# Atomic_V1_0.net
KiCad netlist of a schematic drawn in EAGLE
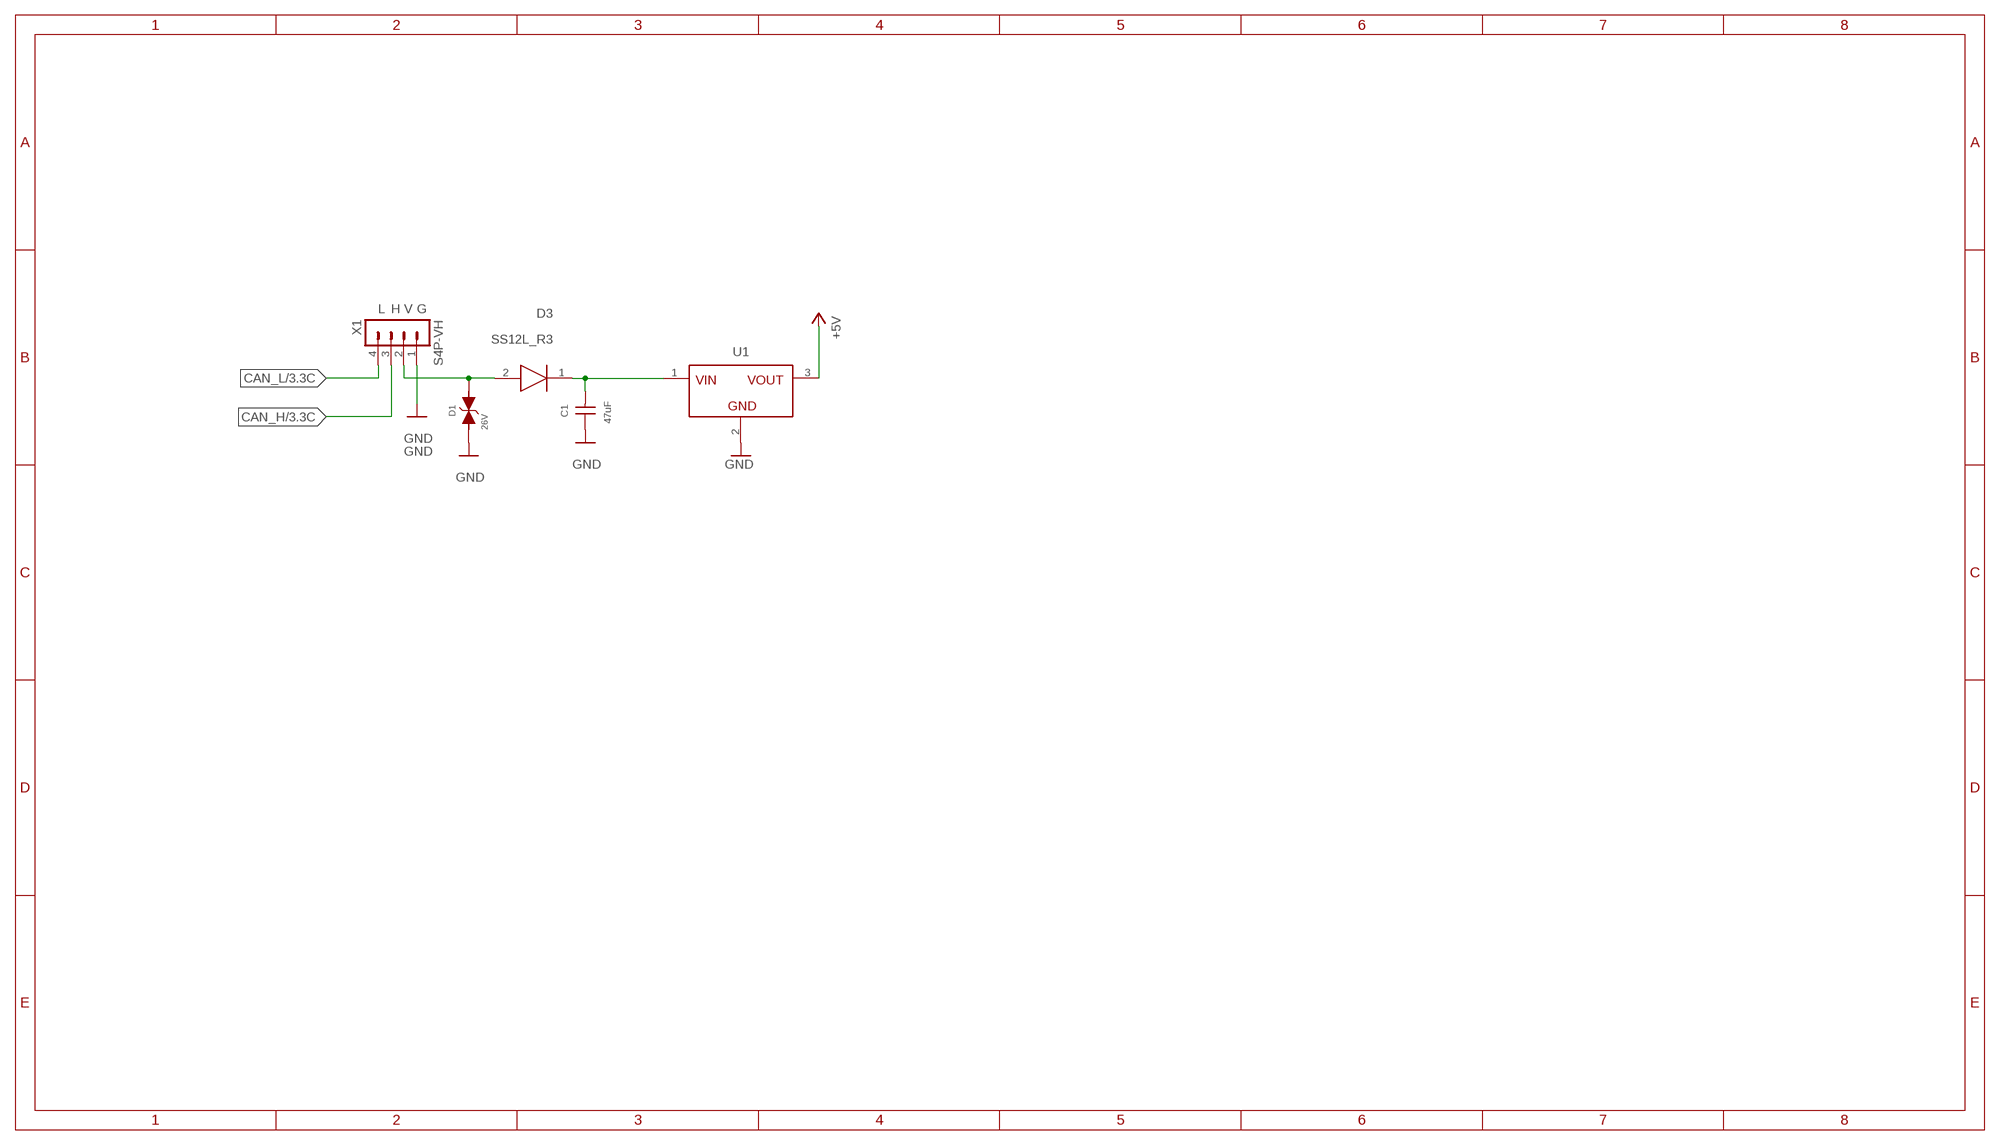
[diagram p0: schematic, sheet 1]
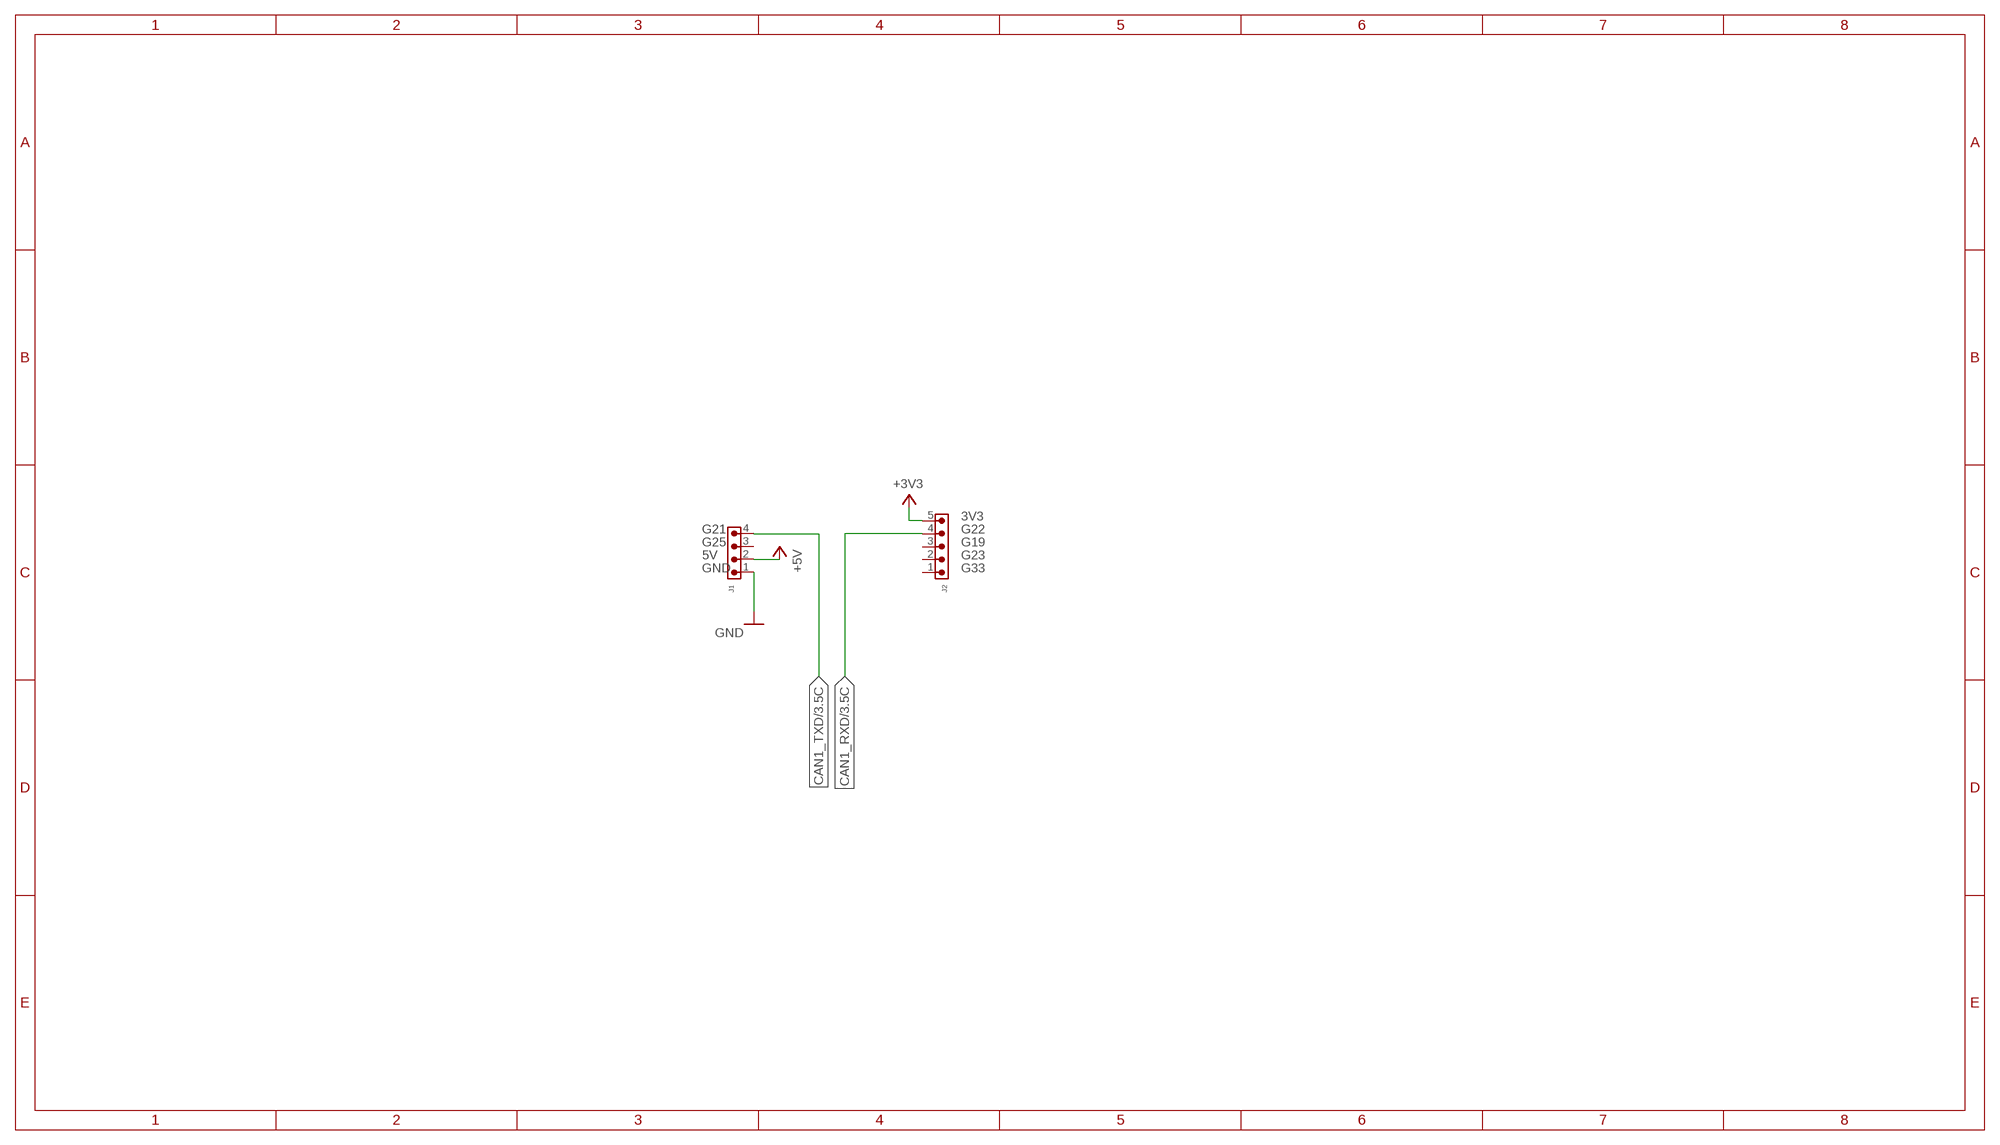
[diagram p1: schematic, sheet 2]
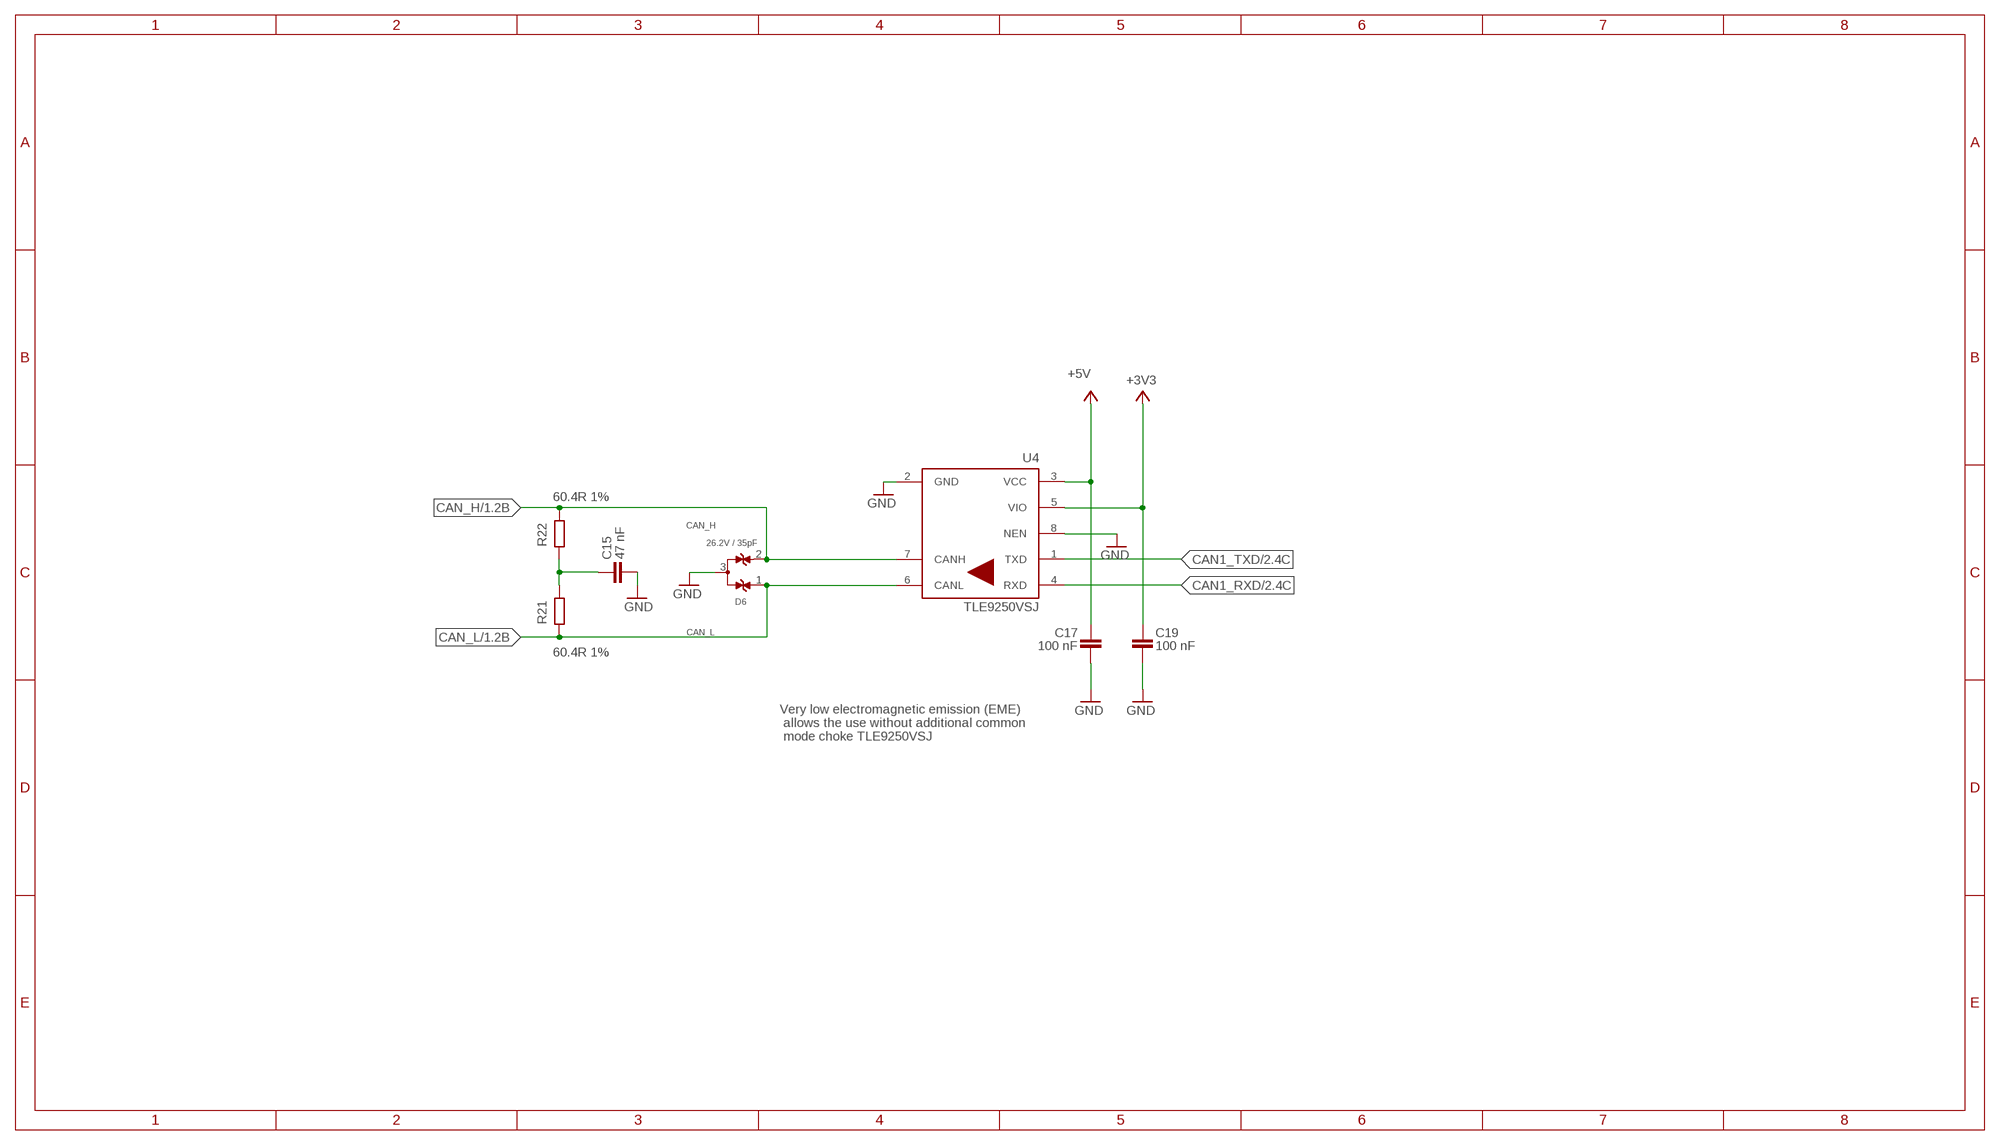
[diagram p2: schematic, sheet 3]

(export (version "E")
  (design (tool "Eeschema 10.0.6"))
  (components
    (comp (ref "C1")
      (value "47uF")
      (footprint "eagle-import:WCAP-CSGP_1210_H2.5")
      (libsource (lib "eagle-import") (part "WCAP-CSGP_1210_H2.5_25V(DC)_885012109014"))
    )
    (comp (ref "D1")
      (value "26V")
      (footprint "eagle-import:WE-TVSP_DO-214AC_BIDIRECTIONAL")
      (libsource (lib "eagle-import") (part "WE-TVSP_DO-214AC_400W_BI_824501261"))
    )
    (comp (ref "D3")
      (value "SS12L_R3")
      (footprint "eagle-import:SODFL3618X143N")
      (fields
        (field (name "MANUFACTURER_PART_NUMBER") "SS12L R3")
        (field (name "MOUSER_PART_NUMBER") "821-SS12LR3")
      )
      (libsource (lib "eagle-import") (part "SS12L_R3"))
    )
    (comp (ref "U1")
      (value "MAGI³C-FDSM_SIP-3_173010542_173XXXX42")
      (footprint "eagle-import:MAGI³C-FDSM_173XXXX42")
      (libsource (lib "eagle-import") (part "MAGI³C-FDSM_SIP-3_173XXXX42_173010542"))
    )
    (comp (ref "X1")
      (value "S4P-VH")
      (footprint "eagle-import:S4P-VH")
      (libsource (lib "eagle-import") (part "S4P-VH"))
    )
    (comp (ref "C15")
      (value "47 nF")
      (footprint "eagle-import:WCAP-CSGP_0402")
      (libsource (lib "eagle-import") (part "WCAP-CSGP_0402_25V(DC)_885012205054"))
    )
    (comp (ref "C17")
      (value "100 nF")
      (footprint "eagle-import:WCAP-CSGP_0402")
      (libsource (lib "eagle-import") (part "WCAP-CSGP_0402_16V(DC)_885012205037"))
    )
    (comp (ref "C19")
      (value "100 nF")
      (footprint "eagle-import:WCAP-CSGP_0402")
      (libsource (lib "eagle-import") (part "WCAP-CSGP_0402_16V(DC)_885012205037"))
    )
    (comp (ref "D6")
      (value "26.2V / 35pF")
      (footprint "eagle-import:WE-TVS_SOT23-3L")
      (libsource (lib "eagle-import") (part "WE-TVS_SOT23-3L_824098024"))
    )
    (comp (ref "R21")
      (value "60.4R 1%")
      (footprint "eagle-import:WCAP-CSRF_0402")
      (fields (field (name "N") "SMD 0402 60.4ohms 1% AEC-Q200"))
      (libsource (lib "eagle-import") (part "R-0402_60.4OHMS_1%_AEC-Q200"))
    )
    (comp (ref "R22")
      (value "60.4R 1%")
      (footprint "eagle-import:WCAP-CSRF_0402")
      (fields (field (name "N") "SMD 0402 60.4ohms 1% AEC-Q200"))
      (libsource (lib "eagle-import") (part "R-0402_60.4OHMS_1%_AEC-Q200"))
    )
    (comp (ref "U4")
      (value "TLE9250VSJ")
      (footprint "eagle-import:SOIC127P602X173-8N-V")
      (libsource (lib "eagle-import") (part "TLE9250VSJ"))
    )
    (comp (ref "J1")
      (value "6130XX11121_61300411121")
      (footprint "eagle-import:61300411121")
      (libsource (lib "eagle-import") (part "6130XX11121_61300411121"))
    )
    (comp (ref "J2")
      (value "6130XX11121_61300511121")
      (footprint "eagle-import:61300511121")
      (libsource (lib "eagle-import") (part "6130XX11121_61300511121"))
    )
  )
  (nets
    (net (code "1") (name "+3V3") (class "Default")
      (node (ref "C19") (pin "1") (pinfunction "1_1") (pintype "passive"))
      (node (ref "J2") (pin "5") (pinfunction "5_5") (pintype "passive"))
      (node (ref "U4") (pin "5") (pinfunction "VIO_5") (pintype "input"))
    )
    (net (code "2") (name "+5V") (class "Default")
      (node (ref "C17") (pin "1") (pinfunction "1_1") (pintype "passive"))
      (node (ref "J1") (pin "2") (pinfunction "2_2") (pintype "passive"))
      (node (ref "U1") (pin "3") (pinfunction "VOUT_3") (pintype "output"))
      (node (ref "U4") (pin "3") (pinfunction "VCC_3") (pintype "input"))
    )
    (net (code "3") (name "CAN1_RXD") (class "Default")
      (node (ref "J2") (pin "4") (pinfunction "4_4") (pintype "passive"))
      (node (ref "U4") (pin "4") (pinfunction "RXD_4") (pintype "output"))
    )
    (net (code "4") (name "CAN1_TXD") (class "Default")
      (node (ref "J1") (pin "4") (pinfunction "4_4") (pintype "passive"))
      (node (ref "U4") (pin "1") (pinfunction "TXD_1") (pintype "input"))
    )
    (net (code "5") (name "CAN_H") (class "Default")
      (node (ref "D6") (pin "2") (pinfunction "2_2") (pintype "passive"))
      (node (ref "R22") (pin "2") (pinfunction "2_2") (pintype "passive"))
      (node (ref "U4") (pin "7") (pinfunction "CANH_7") (pintype "bidirectional"))
      (node (ref "X1") (pin "3") (pinfunction "3_3") (pintype "passive"))
    )
    (net (code "6") (name "CAN_L") (class "Default")
      (node (ref "D6") (pin "1") (pinfunction "1_1") (pintype "passive"))
      (node (ref "R21") (pin "1") (pinfunction "1_1") (pintype "passive"))
      (node (ref "U4") (pin "6") (pinfunction "CANL_6") (pintype "bidirectional"))
      (node (ref "X1") (pin "4") (pinfunction "4_4") (pintype "passive"))
    )
    (net (code "7") (name "GND") (class "Default")
      (node (ref "C1") (pin "1") (pinfunction "1_1") (pintype "passive"))
      (node (ref "C15") (pin "2") (pinfunction "2_2") (pintype "passive"))
      (node (ref "C17") (pin "2") (pinfunction "2_2") (pintype "passive"))
      (node (ref "C19") (pin "2") (pinfunction "2_2") (pintype "passive"))
      (node (ref "D1") (pin "1") (pinfunction "1_1") (pintype "passive"))
      (node (ref "D6") (pin "3") (pinfunction "3_3") (pintype "passive"))
      (node (ref "J1") (pin "1") (pinfunction "1_1") (pintype "passive"))
      (node (ref "U1") (pin "2") (pinfunction "GND_2") (pintype "passive"))
      (node (ref "U4") (pin "2") (pinfunction "GND_2") (pintype "power_in"))
      (node (ref "U4") (pin "8") (pinfunction "NEN_8") (pintype "input"))
      (node (ref "X1") (pin "1") (pinfunction "1_1") (pintype "passive"))
    )
    (net (code "8") (name "Net-(C15-Pad1)") (class "Default")
      (node (ref "C15") (pin "1") (pinfunction "1_1") (pintype "passive"))
      (node (ref "R21") (pin "2") (pinfunction "2_2") (pintype "passive"))
      (node (ref "R22") (pin "1") (pinfunction "1_1") (pintype "passive"))
    )
    (net (code "9") (name "Net-(D3-A)") (class "Default")
      (node (ref "D1") (pin "2") (pinfunction "2_2") (pintype "passive"))
      (node (ref "D3") (pin "2") (pinfunction "A_2") (pintype "bidirectional"))
      (node (ref "X1") (pin "2") (pinfunction "2_2") (pintype "passive"))
    )
    (net (code "10") (name "Net-(D3-K)") (class "Default")
      (node (ref "C1") (pin "2") (pinfunction "2_2") (pintype "passive"))
      (node (ref "D3") (pin "1") (pinfunction "K_1") (pintype "bidirectional"))
      (node (ref "U1") (pin "1") (pinfunction "VIN_1") (pintype "input"))
    )
    (net (code "11") (name "unconnected-(J1-Pad3)") (class "Default")
      (node (ref "J1") (pin "3") (pinfunction "3_3") (pintype "passive"))
    )
    (net (code "12") (name "unconnected-(J2-Pad1)") (class "Default")
      (node (ref "J2") (pin "1") (pinfunction "1_1") (pintype "passive"))
    )
    (net (code "13") (name "unconnected-(J2-Pad2)") (class "Default")
      (node (ref "J2") (pin "2") (pinfunction "2_2") (pintype "passive"))
    )
    (net (code "14") (name "unconnected-(J2-Pad3)") (class "Default")
      (node (ref "J2") (pin "3") (pinfunction "3_3") (pintype "passive"))
    )
  )
)
